# BPMLabLineRX2.net
KiCad netlist of a schematic drawn in EAGLE
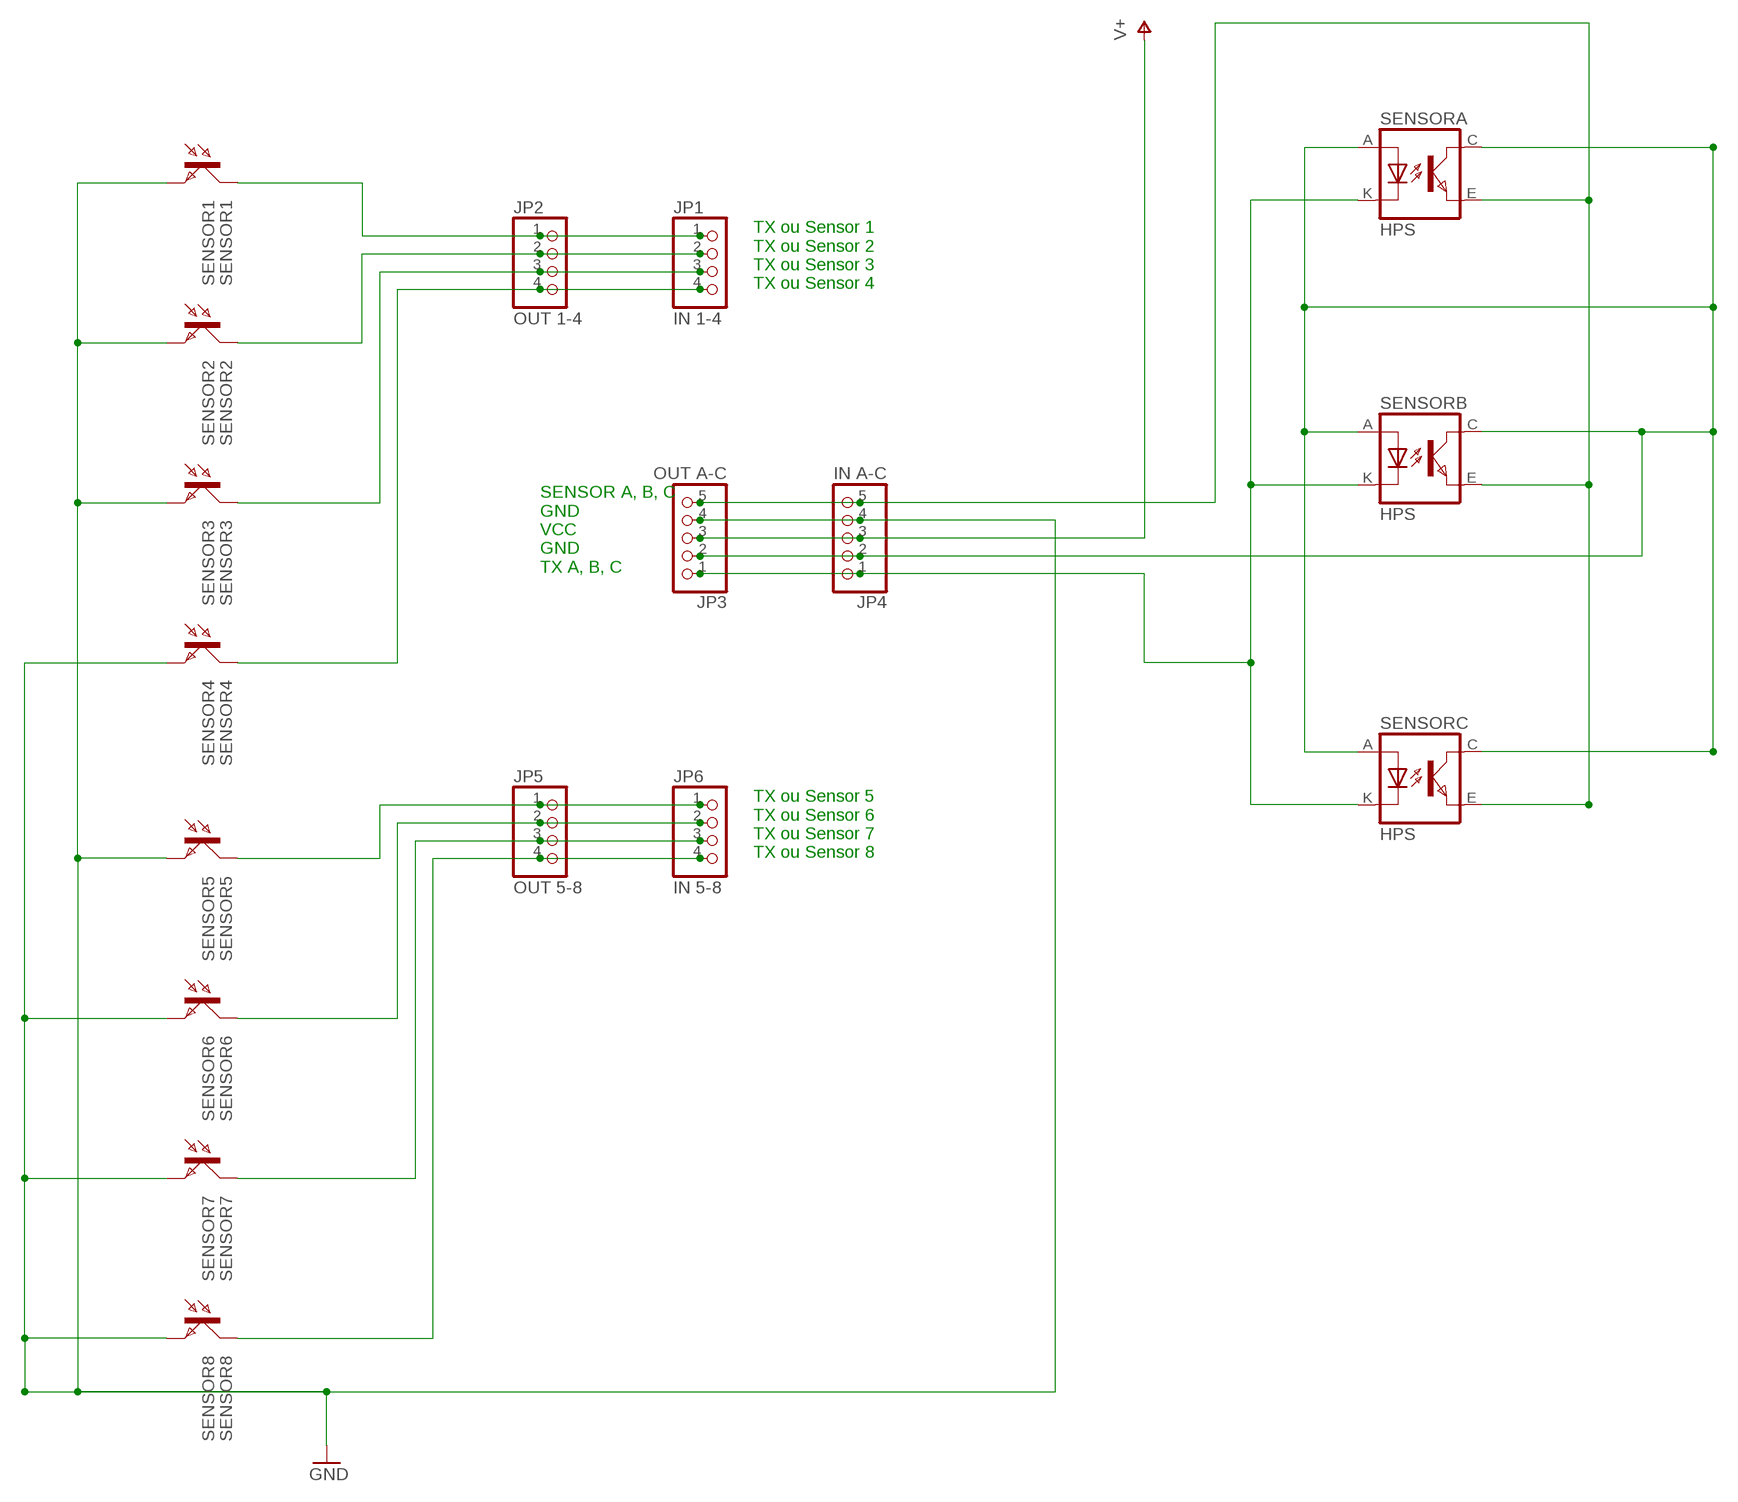
[diagram p0: schematic, sheet 1]

(export (version "E")
  (design (tool "Eeschema 10.0.6"))
  (components
    (comp (ref "JP1")
      (value "IN 1-4")
      (footprint "eagle-import:1X04")
      (libsource (lib "eagle-import") (part "PINHD-1X4"))
    )
    (comp (ref "JP2")
      (value "OUT 1-4")
      (footprint "eagle-import:1X04")
      (libsource (lib "eagle-import") (part "PINHD-1X4"))
    )
    (comp (ref "JP3")
      (value "OUT A-C")
      (footprint "eagle-import:1X05")
      (libsource (lib "eagle-import") (part "PINHD-1X5"))
    )
    (comp (ref "JP4")
      (value "IN A-C")
      (footprint "eagle-import:1X05")
      (libsource (lib "eagle-import") (part "PINHD-1X5"))
    )
    (comp (ref "JP5")
      (value "OUT 5-8")
      (footprint "eagle-import:1X04")
      (libsource (lib "eagle-import") (part "PINHD-1X4"))
    )
    (comp (ref "JP6")
      (value "IN 5-8")
      (footprint "eagle-import:1X04")
      (libsource (lib "eagle-import") (part "PINHD-1X4"))
    )
    (comp (ref "SENSOR1")
      (value "SENSOR1")
      (footprint "eagle-import:BPX81")
      (libsource (lib "eagle-import") (part "BPX81"))
    )
    (comp (ref "SENSOR2")
      (value "SENSOR2")
      (footprint "eagle-import:BPX81")
      (libsource (lib "eagle-import") (part "BPX81"))
    )
    (comp (ref "SENSOR3")
      (value "SENSOR3")
      (footprint "eagle-import:BPX81")
      (libsource (lib "eagle-import") (part "BPX81"))
    )
    (comp (ref "SENSOR4")
      (value "SENSOR4")
      (footprint "eagle-import:BPX81")
      (libsource (lib "eagle-import") (part "BPX81"))
    )
    (comp (ref "SENSOR5")
      (value "SENSOR5")
      (footprint "eagle-import:BPX81")
      (libsource (lib "eagle-import") (part "BPX81"))
    )
    (comp (ref "SENSOR6")
      (value "SENSOR6")
      (footprint "eagle-import:BPX81")
      (libsource (lib "eagle-import") (part "BPX81"))
    )
    (comp (ref "SENSOR7")
      (value "SENSOR7")
      (footprint "eagle-import:BPX81")
      (libsource (lib "eagle-import") (part "BPX81"))
    )
    (comp (ref "SENSOR8")
      (value "SENSOR8")
      (footprint "eagle-import:BPX81")
      (libsource (lib "eagle-import") (part "BPX81"))
    )
    (comp (ref "SENSORA")
      (value "HPS")
      (footprint "eagle-import:TCRT5000")
      (libsource (lib "eagle-import") (part "TCRT5000"))
    )
    (comp (ref "SENSORB")
      (value "HPS")
      (footprint "eagle-import:TCRT5000")
      (libsource (lib "eagle-import") (part "TCRT5000"))
    )
    (comp (ref "SENSORC")
      (value "HPS")
      (footprint "eagle-import:TCRT5000")
      (libsource (lib "eagle-import") (part "TCRT5000"))
    )
  )
  (nets
    (net (code "1") (name "GND") (class "Default")
      (node (ref "JP3") (pin "4") (pinfunction "4_4") (pintype "passive"))
      (node (ref "JP4") (pin "4") (pinfunction "4_4") (pintype "passive"))
      (node (ref "SENSOR1") (pin "E") (pinfunction "E_E") (pintype "passive"))
      (node (ref "SENSOR2") (pin "E") (pinfunction "E_E") (pintype "passive"))
      (node (ref "SENSOR3") (pin "E") (pinfunction "E_E") (pintype "passive"))
      (node (ref "SENSOR4") (pin "E") (pinfunction "E_E") (pintype "passive"))
      (node (ref "SENSOR5") (pin "E") (pinfunction "E_E") (pintype "passive"))
      (node (ref "SENSOR6") (pin "E") (pinfunction "E_E") (pintype "passive"))
      (node (ref "SENSOR7") (pin "E") (pinfunction "E_E") (pintype "passive"))
      (node (ref "SENSOR8") (pin "E") (pinfunction "E_E") (pintype "passive"))
    )
    (net (code "2") (name "Net-(JP1-Pad1)") (class "Default")
      (node (ref "JP1") (pin "1") (pinfunction "1_1") (pintype "passive"))
      (node (ref "JP2") (pin "1") (pinfunction "1_1") (pintype "passive"))
      (node (ref "SENSOR1") (pin "C") (pinfunction "C_C") (pintype "passive"))
    )
    (net (code "3") (name "Net-(JP1-Pad2)") (class "Default")
      (node (ref "JP1") (pin "2") (pinfunction "2_2") (pintype "passive"))
      (node (ref "JP2") (pin "2") (pinfunction "2_2") (pintype "passive"))
      (node (ref "SENSOR2") (pin "C") (pinfunction "C_C") (pintype "passive"))
    )
    (net (code "4") (name "Net-(JP1-Pad3)") (class "Default")
      (node (ref "JP1") (pin "3") (pinfunction "3_3") (pintype "passive"))
      (node (ref "JP2") (pin "3") (pinfunction "3_3") (pintype "passive"))
      (node (ref "SENSOR3") (pin "C") (pinfunction "C_C") (pintype "passive"))
    )
    (net (code "5") (name "Net-(JP1-Pad4)") (class "Default")
      (node (ref "JP1") (pin "4") (pinfunction "4_4") (pintype "passive"))
      (node (ref "JP2") (pin "4") (pinfunction "4_4") (pintype "passive"))
      (node (ref "SENSOR4") (pin "C") (pinfunction "C_C") (pintype "passive"))
    )
    (net (code "6") (name "Net-(JP5-Pad1)") (class "Default")
      (node (ref "JP5") (pin "1") (pinfunction "1_1") (pintype "passive"))
      (node (ref "JP6") (pin "1") (pinfunction "1_1") (pintype "passive"))
      (node (ref "SENSOR5") (pin "C") (pinfunction "C_C") (pintype "passive"))
    )
    (net (code "7") (name "Net-(JP5-Pad2)") (class "Default")
      (node (ref "JP5") (pin "2") (pinfunction "2_2") (pintype "passive"))
      (node (ref "JP6") (pin "2") (pinfunction "2_2") (pintype "passive"))
      (node (ref "SENSOR6") (pin "C") (pinfunction "C_C") (pintype "passive"))
    )
    (net (code "8") (name "Net-(JP5-Pad3)") (class "Default")
      (node (ref "JP5") (pin "3") (pinfunction "3_3") (pintype "passive"))
      (node (ref "JP6") (pin "3") (pinfunction "3_3") (pintype "passive"))
      (node (ref "SENSOR7") (pin "C") (pinfunction "C_C") (pintype "passive"))
    )
    (net (code "9") (name "Net-(JP5-Pad4)") (class "Default")
      (node (ref "JP5") (pin "4") (pinfunction "4_4") (pintype "passive"))
      (node (ref "JP6") (pin "4") (pinfunction "4_4") (pintype "passive"))
      (node (ref "SENSOR8") (pin "C") (pinfunction "C_C") (pintype "passive"))
    )
    (net (code "10") (name "Net-(SENSORA-ANODE)") (class "Default")
      (node (ref "JP3") (pin "2") (pinfunction "2_2") (pintype "passive"))
      (node (ref "JP4") (pin "2") (pinfunction "2_2") (pintype "passive"))
      (node (ref "SENSORA") (pin "A") (pinfunction "ANODE_A") (pintype "passive"))
      (node (ref "SENSORA") (pin "C") (pinfunction "COLLECTOR_C") (pintype "passive"))
      (node (ref "SENSORB") (pin "A") (pinfunction "ANODE_A") (pintype "passive"))
      (node (ref "SENSORB") (pin "C") (pinfunction "COLLECTOR_C") (pintype "passive"))
      (node (ref "SENSORC") (pin "A") (pinfunction "ANODE_A") (pintype "passive"))
      (node (ref "SENSORC") (pin "C") (pinfunction "COLLECTOR_C") (pintype "passive"))
    )
    (net (code "11") (name "Net-(SENSORA-CATHODE)") (class "Default")
      (node (ref "JP3") (pin "1") (pinfunction "1_1") (pintype "passive"))
      (node (ref "JP4") (pin "1") (pinfunction "1_1") (pintype "passive"))
      (node (ref "SENSORA") (pin "K") (pinfunction "CATHODE_K") (pintype "passive"))
      (node (ref "SENSORB") (pin "K") (pinfunction "CATHODE_K") (pintype "passive"))
      (node (ref "SENSORC") (pin "K") (pinfunction "CATHODE_K") (pintype "passive"))
    )
    (net (code "12") (name "Net-(SENSORA-EMITTER)") (class "Default")
      (node (ref "JP3") (pin "5") (pinfunction "5_5") (pintype "passive"))
      (node (ref "JP4") (pin "5") (pinfunction "5_5") (pintype "passive"))
      (node (ref "SENSORA") (pin "E") (pinfunction "EMITTER_E") (pintype "passive"))
      (node (ref "SENSORB") (pin "E") (pinfunction "EMITTER_E") (pintype "passive"))
      (node (ref "SENSORC") (pin "E") (pinfunction "EMITTER_E") (pintype "passive"))
    )
    (net (code "13") (name "V+") (class "Default")
      (node (ref "JP3") (pin "3") (pinfunction "3_3") (pintype "passive"))
      (node (ref "JP4") (pin "3") (pinfunction "3_3") (pintype "passive"))
    )
  )
)
